# WalkSensor_V3_0.net
KiCad netlist of a schematic drawn in EAGLE
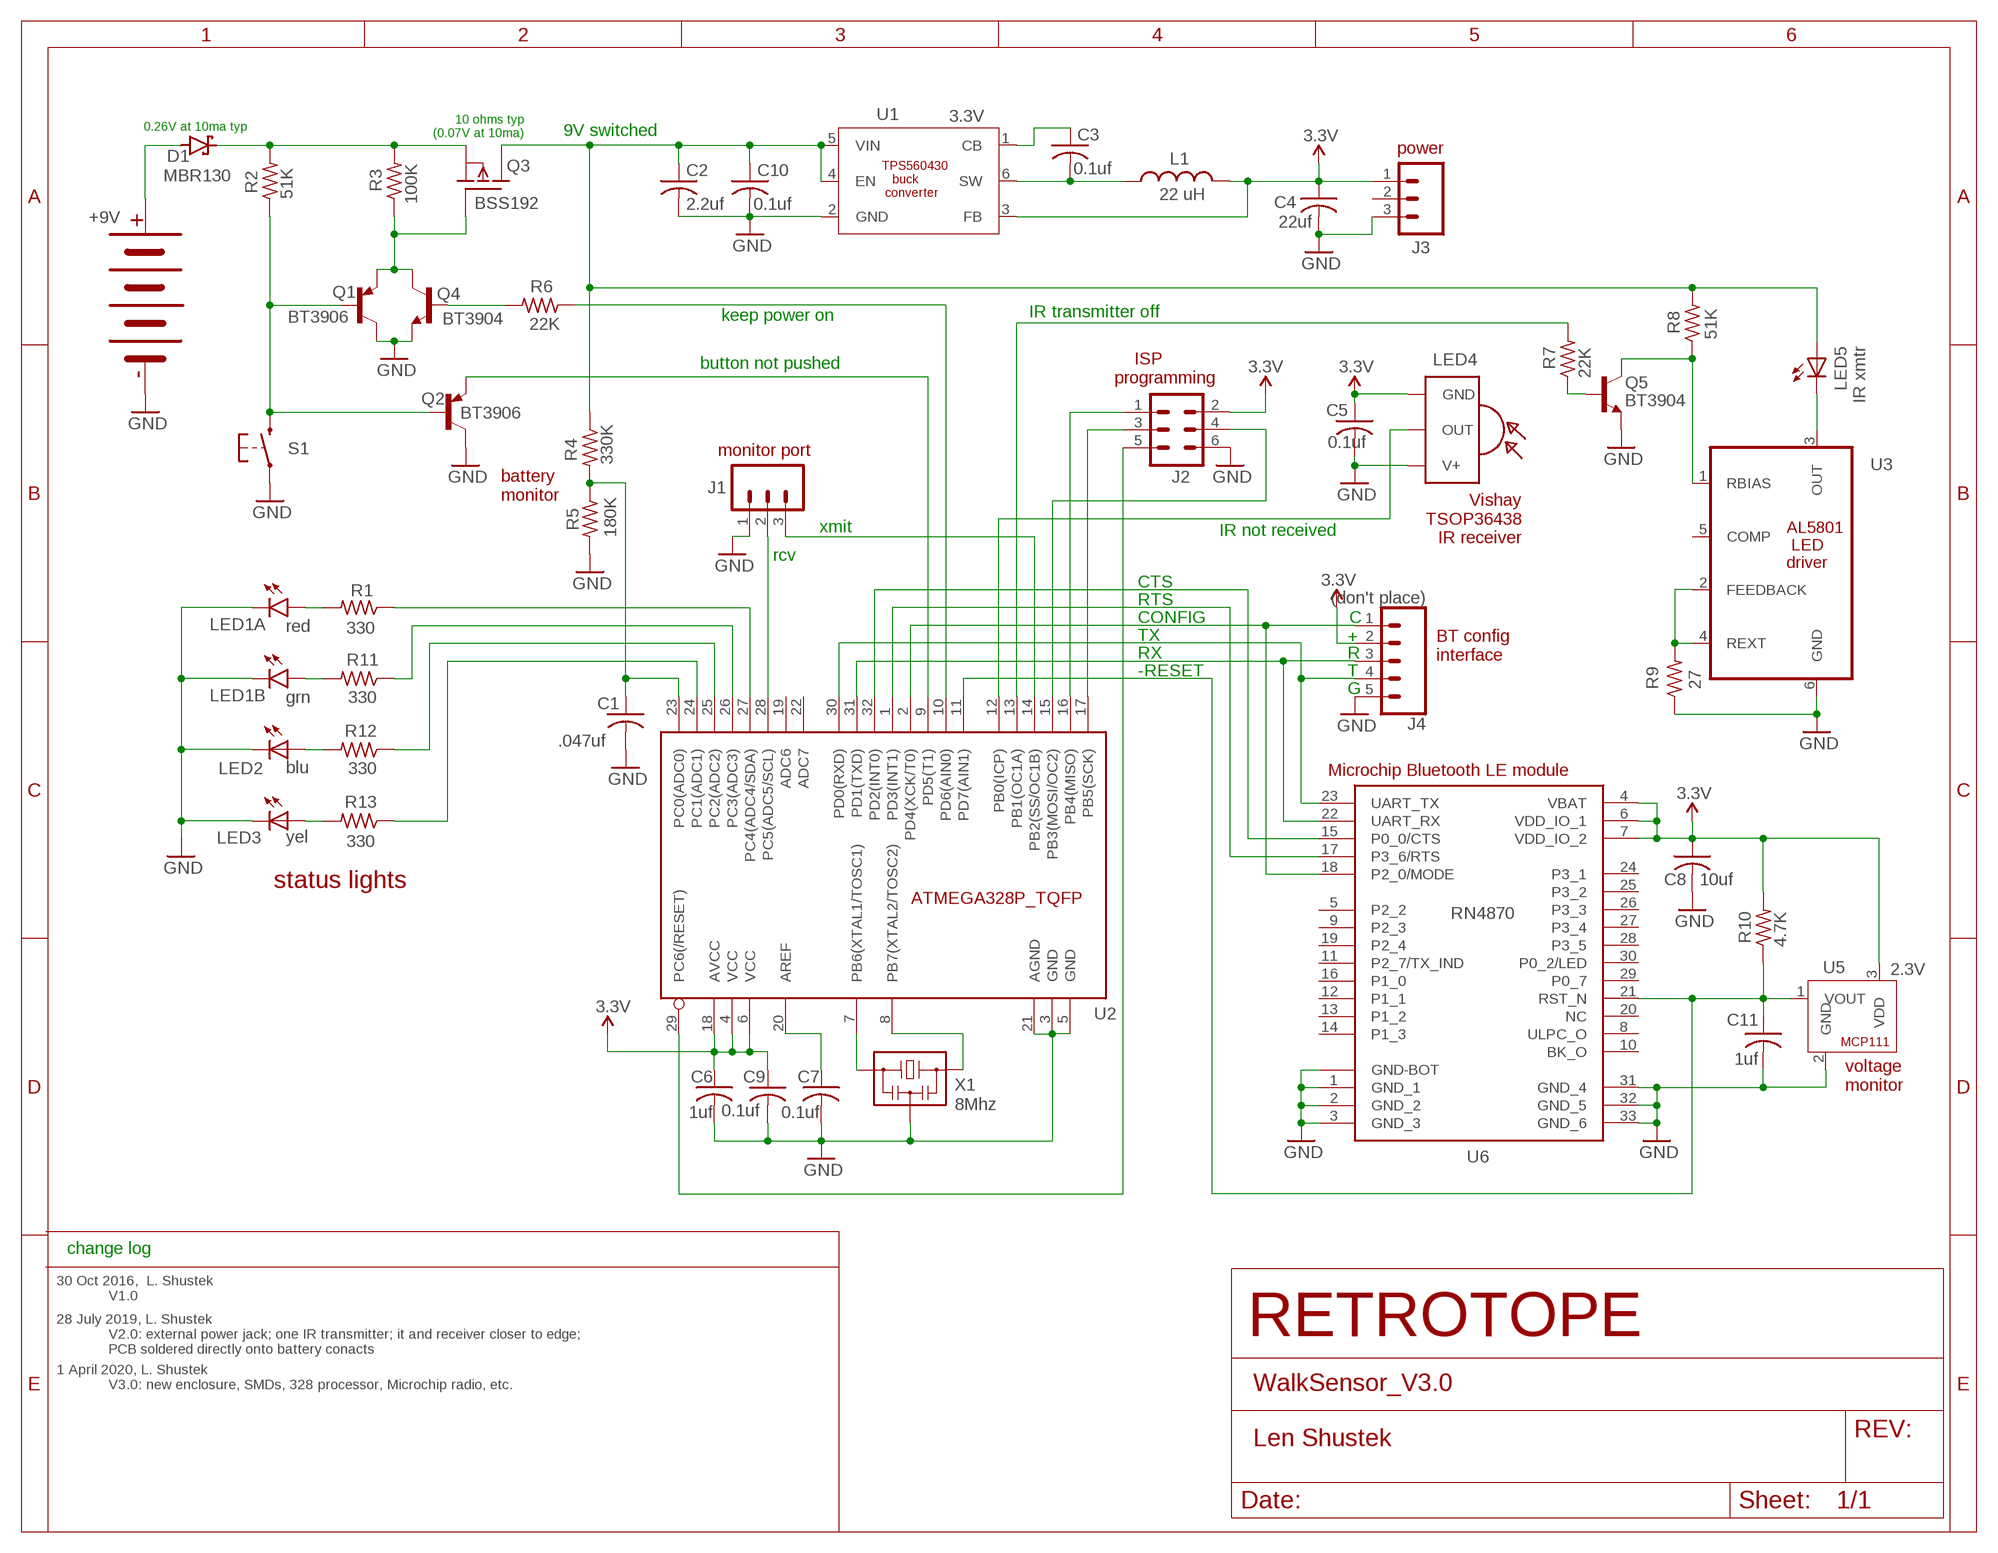
[diagram p0: schematic, sheet 1]

(export (version "E")
  (design (tool "Eeschema 10.0.6"))
  (components
    (comp (ref "B1")
      (value "9V battery wires")
      (footprint "eagle-import:4-CELL-BATTERY")
      (libsource (lib "eagle-import") (part "4-CELL-BATTERY"))
    )
    (comp (ref "C1")
      (value ".047uf")
      (footprint "eagle-import:C0805")
      (libsource (lib "eagle-import") (part "C-USC0805"))
    )
    (comp (ref "C2")
      (value "2.2uf")
      (footprint "eagle-import:C1210")
      (libsource (lib "eagle-import") (part "C-USC1210"))
    )
    (comp (ref "C3")
      (value "0.1uf")
      (footprint "eagle-import:C0805")
      (libsource (lib "eagle-import") (part "C-USC0805"))
    )
    (comp (ref "C4")
      (value "22uf")
      (footprint "eagle-import:C1210")
      (libsource (lib "eagle-import") (part "C-USC1210"))
    )
    (comp (ref "C5")
      (value "0.1uf")
      (footprint "eagle-import:C0805")
      (libsource (lib "eagle-import") (part "C-USC0805"))
    )
    (comp (ref "C6")
      (value "1uf")
      (footprint "eagle-import:C0805")
      (libsource (lib "eagle-import") (part "C-USC0805"))
    )
    (comp (ref "C7")
      (value "0.1uf")
      (footprint "eagle-import:C0805")
      (libsource (lib "eagle-import") (part "C-USC0805"))
    )
    (comp (ref "C8")
      (value "10uf")
      (footprint "eagle-import:C1210")
      (libsource (lib "eagle-import") (part "C-USC1210"))
    )
    (comp (ref "C9")
      (value "0.1uf")
      (footprint "eagle-import:C0805")
      (libsource (lib "eagle-import") (part "C-USC0805"))
    )
    (comp (ref "C10")
      (value "0.1uf")
      (footprint "eagle-import:C0805")
      (libsource (lib "eagle-import") (part "C-USC0805"))
    )
    (comp (ref "C11")
      (value "1uf")
      (footprint "eagle-import:C0805")
      (libsource (lib "eagle-import") (part "C-USC0805"))
    )
    (comp (ref "D1")
      (value "MBR130")
      (footprint "eagle-import:SOD123-2")
      (libsource (lib "eagle-import") (part "DIODE,SCHOTTKY"))
    )
    (comp (ref "J1")
      (value "(don't place)")
      (footprint "eagle-import:1X03")
      (libsource (lib "eagle-import") (part "CONN_03"))
    )
    (comp (ref "J2")
      (value "ISP pgm connector")
      (footprint "eagle-import:2X3_SMT")
      (libsource (lib "eagle-import") (part "CONN_03X22X3_SMT"))
    )
    (comp (ref "J3")
      (value "(don't place)")
      (footprint "eagle-import:1X03")
      (libsource (lib "eagle-import") (part "CONN_03"))
    )
    (comp (ref "J4")
      (value "(don't place)")
      (footprint "eagle-import:1X05")
      (libsource (lib "eagle-import") (part "CONN_05"))
    )
    (comp (ref "L1")
      (value "22 uH")
      (footprint "eagle-import:L1812")
      (libsource (lib "eagle-import") (part "L-USL1812"))
    )
    (comp (ref "LED1")
      (value "red/grn")
      (footprint "eagle-import:P-LCC4-1")
      (libsource (lib "eagle-import") (part "LED_DUALP-LCC4-1"))
    )
    (comp (ref "LED2")
      (value "blu")
      (footprint "eagle-import:LED_PLCC-2")
      (libsource (lib "eagle-import") (part "LEDPLCC-2"))
    )
    (comp (ref "LED3")
      (value "yel")
      (footprint "eagle-import:LED_PLCC-2")
      (libsource (lib "eagle-import") (part "LEDPLCC-2"))
    )
    (comp (ref "LED4")
      (value "IR rcvr")
      (footprint "eagle-import:VISHAY_TSOP_SMD_SIDE")
      (libsource (lib "eagle-import") (part "IR_RCVRVISHAY_TSOP_SMD_SIDE"))
    )
    (comp (ref "LED5")
      (value "IR xmtr")
      (footprint "eagle-import:LED_VISHAY_VSMB2948")
      (libsource (lib "eagle-import") (part "LEDLED_VISHAY_VSMB2948"))
    )
    (comp (ref "Q1")
      (value "BT3906")
      (footprint "eagle-import:SOT23-3")
      (libsource (lib "eagle-import") (part "PNP_TRANSISTORSOT23-3"))
    )
    (comp (ref "Q2")
      (value "BT3906")
      (footprint "eagle-import:SOT23-3")
      (libsource (lib "eagle-import") (part "PNP_TRANSISTORSOT23-3"))
    )
    (comp (ref "Q3")
      (value "BSS192")
      (footprint "eagle-import:SOT89")
      (libsource (lib "eagle-import") (part "VP3203SOP89"))
    )
    (comp (ref "Q4")
      (value "BT3904")
      (footprint "eagle-import:SOT23-3")
      (libsource (lib "eagle-import") (part "NPN-TRANSISTORSOT23-3"))
    )
    (comp (ref "Q5")
      (value "BT3904")
      (footprint "eagle-import:SOT23-3")
      (libsource (lib "eagle-import") (part "NPN-TRANSISTORSOT23-3"))
    )
    (comp (ref "R1")
      (value "330")
      (footprint "eagle-import:M0805")
      (libsource (lib "eagle-import") (part "R-US_M0805"))
    )
    (comp (ref "R2")
      (value "51K")
      (footprint "eagle-import:M0805")
      (libsource (lib "eagle-import") (part "R-US_M0805"))
    )
    (comp (ref "R3")
      (value "100K")
      (footprint "eagle-import:M0805")
      (libsource (lib "eagle-import") (part "R-US_M0805"))
    )
    (comp (ref "R4")
      (value "330K")
      (footprint "eagle-import:M0805")
      (libsource (lib "eagle-import") (part "R-US_M0805"))
    )
    (comp (ref "R5")
      (value "180K")
      (footprint "eagle-import:M0805")
      (libsource (lib "eagle-import") (part "R-US_M0805"))
    )
    (comp (ref "R6")
      (value "22K")
      (footprint "eagle-import:M0805")
      (libsource (lib "eagle-import") (part "R-US_M0805"))
    )
    (comp (ref "R7")
      (value "22K")
      (footprint "eagle-import:M0805")
      (libsource (lib "eagle-import") (part "R-US_M0805"))
    )
    (comp (ref "R8")
      (value "51K")
      (footprint "eagle-import:M0805")
      (libsource (lib "eagle-import") (part "R-US_M0805"))
    )
    (comp (ref "R9")
      (value "27")
      (footprint "eagle-import:M0805")
      (libsource (lib "eagle-import") (part "R-US_M0805"))
    )
    (comp (ref "R10")
      (value "4.7K")
      (footprint "eagle-import:M0805")
      (libsource (lib "eagle-import") (part "R-US_M0805"))
    )
    (comp (ref "R11")
      (value "330")
      (footprint "eagle-import:M0805")
      (libsource (lib "eagle-import") (part "R-US_M0805"))
    )
    (comp (ref "R12")
      (value "330")
      (footprint "eagle-import:M0805")
      (libsource (lib "eagle-import") (part "R-US_M0805"))
    )
    (comp (ref "R13")
      (value "330")
      (footprint "eagle-import:M0805")
      (libsource (lib "eagle-import") (part "R-US_M0805"))
    )
    (comp (ref "S1")
      (value "pushbutton")
      (footprint "eagle-import:SWITCH_C&K_GULLWING")
      (libsource (lib "eagle-import") (part "PUSHBUTTON-SPSTC&K_GULLWING"))
    )
    (comp (ref "U1")
      (value "3.3V")
      (footprint "eagle-import:SOT23-6")
      (libsource (lib "eagle-import") (part "TPS560430"))
    )
    (comp (ref "U2")
      (value "ATMEGA328P_TQFP")
      (footprint "eagle-import:TQFP32-08")
      (libsource (lib "eagle-import") (part "ATMEGA328P_TQFP"))
    )
    (comp (ref "U3")
      (value "AL5801")
      (footprint "eagle-import:SOT95P280X130-6N")
      (fields (field (name "MPN") "ZXGD3005E6TA"))
      (libsource (lib "eagle-import") (part "AL5801"))
    )
    (comp (ref "U5")
      (value "2.3V")
      (footprint "eagle-import:SC70-3-R")
      (libsource (lib "eagle-import") (part "MCP111SC-70"))
    )
    (comp (ref "U6")
      (value "RN4870")
      (footprint "eagle-import:RN4870")
      (libsource (lib "eagle-import") (part "RN4870-V_RM118LJS1"))
    )
    (comp (ref "X1")
      (value "8Mhz")
      (footprint "eagle-import:CSTNE")
      (libsource (lib "eagle-import") (part "CSTCRCSTNE"))
    )
  )
  (nets
    (net (code "1") (name "3.3V") (class "Default")
      (node (ref "C4") (pin "1") (pinfunction "1_1") (pintype "passive"))
      (node (ref "C5") (pin "1") (pinfunction "1_1") (pintype "passive"))
      (node (ref "C6") (pin "1") (pinfunction "1_1") (pintype "passive"))
      (node (ref "C8") (pin "1") (pinfunction "1_1") (pintype "passive"))
      (node (ref "C9") (pin "1") (pinfunction "1_1") (pintype "passive"))
      (node (ref "J2") (pin "2") (pinfunction "2_2") (pintype "bidirectional"))
      (node (ref "J3") (pin "1") (pinfunction "1_1") (pintype "passive"))
      (node (ref "J4") (pin "2") (pinfunction "2_2") (pintype "passive"))
      (node (ref "L1") (pin "2") (pinfunction "2_2") (pintype "passive"))
      (node (ref "LED4") (pin "P$1") (pinfunction "GND_P$1") (pintype "bidirectional"))
      (node (ref "R10") (pin "2") (pinfunction "2_2") (pintype "passive"))
      (node (ref "U1") (pin "3") (pinfunction "FB_3") (pintype "bidirectional"))
      (node (ref "U2") (pin "18") (pinfunction "AVCC_18") (pintype "bidirectional"))
      (node (ref "U2") (pin "4") (pinfunction "VCC_4") (pintype "bidirectional"))
      (node (ref "U2") (pin "6") (pinfunction "VCC_6") (pintype "bidirectional"))
      (node (ref "U5") (pin "3") (pinfunction "VDD_3") (pintype "bidirectional"))
      (node (ref "U6") (pin "4") (pinfunction "VBAT_4") (pintype "power_in"))
      (node (ref "U6") (pin "6") (pinfunction "VDD_IO_1_6") (pintype "power_in"))
      (node (ref "U6") (pin "7") (pinfunction "VDD_IO_2_7") (pintype "power_in"))
    )
    (net (code "2") (name "GND") (class "Default")
      (node (ref "B1") (pin "P$1") (pinfunction "P$1_P$1") (pintype "bidirectional"))
      (node (ref "C1") (pin "2") (pinfunction "2_2") (pintype "passive"))
      (node (ref "C10") (pin "2") (pinfunction "2_2") (pintype "passive"))
      (node (ref "C11") (pin "2") (pinfunction "2_2") (pintype "passive"))
      (node (ref "C2") (pin "2") (pinfunction "2_2") (pintype "passive"))
      (node (ref "C4") (pin "2") (pinfunction "2_2") (pintype "passive"))
      (node (ref "C5") (pin "2") (pinfunction "2_2") (pintype "passive"))
      (node (ref "C6") (pin "2") (pinfunction "2_2") (pintype "passive"))
      (node (ref "C7") (pin "2") (pinfunction "2_2") (pintype "passive"))
      (node (ref "C8") (pin "2") (pinfunction "2_2") (pintype "passive"))
      (node (ref "C9") (pin "2") (pinfunction "2_2") (pintype "passive"))
      (node (ref "J1") (pin "1") (pinfunction "1_1") (pintype "passive"))
      (node (ref "J2") (pin "6") (pinfunction "6_6") (pintype "bidirectional"))
      (node (ref "J3") (pin "3") (pinfunction "3_3") (pintype "passive"))
      (node (ref "J4") (pin "5") (pinfunction "5_5") (pintype "passive"))
      (node (ref "LED1") (pin "P$1") (pinfunction "C_P$1") (pintype "passive"))
      (node (ref "LED1") (pin "P$4") (pinfunction "C_P$4") (pintype "passive"))
      (node (ref "LED2") (pin "P$2") (pinfunction "C_P$2") (pintype "passive"))
      (node (ref "LED3") (pin "P$2") (pinfunction "C_P$2") (pintype "passive"))
      (node (ref "LED4") (pin "P$3") (pinfunction "V+_P$3") (pintype "bidirectional"))
      (node (ref "Q1") (pin "3") (pinfunction "C_3") (pintype "passive"))
      (node (ref "Q2") (pin "3") (pinfunction "C_3") (pintype "passive"))
      (node (ref "Q4") (pin "2") (pinfunction "E_2") (pintype "passive"))
      (node (ref "Q5") (pin "2") (pinfunction "E_2") (pintype "passive"))
      (node (ref "R5") (pin "2") (pinfunction "2_2") (pintype "passive"))
      (node (ref "R9") (pin "1") (pinfunction "1_1") (pintype "passive"))
      (node (ref "S1") (pin "P$1") (pinfunction "1_P$1") (pintype "passive"))
      (node (ref "S1") (pin "P$2") (pinfunction "1_P$2") (pintype "passive"))
      (node (ref "U1") (pin "2") (pinfunction "GND_2") (pintype "bidirectional"))
      (node (ref "U2") (pin "21") (pinfunction "AGND_21") (pintype "bidirectional"))
      (node (ref "U2") (pin "3") (pinfunction "GND_3") (pintype "bidirectional"))
      (node (ref "U2") (pin "5") (pinfunction "GND_5") (pintype "bidirectional"))
      (node (ref "U3") (pin "6") (pinfunction "GND_6") (pintype "power_in"))
      (node (ref "U5") (pin "2") (pinfunction "GND_2") (pintype "bidirectional"))
      (node (ref "U6") (pin "1") (pinfunction "GND_1_1") (pintype "power_in"))
      (node (ref "U6") (pin "2") (pinfunction "GND_2_2") (pintype "power_in"))
      (node (ref "U6") (pin "3") (pinfunction "GND_3_3") (pintype "power_in"))
      (node (ref "U6") (pin "31") (pinfunction "GND_4_31") (pintype "power_in"))
      (node (ref "U6") (pin "32") (pinfunction "GND_5_32") (pintype "power_in"))
      (node (ref "U6") (pin "33") (pinfunction "GND_6_33") (pintype "power_in"))
      (node (ref "U6") (pin "GND") (pinfunction "GND-BOT_GND") (pintype "power_in"))
      (node (ref "X1") (pin "P$2") (pinfunction "2_P$2") (pintype "passive"))
    )
    (net (code "3") (name "Net-(D1-A)") (class "Default")
      (node (ref "B1") (pin "P$2") (pinfunction "P$2_P$2") (pintype "bidirectional"))
      (node (ref "D1") (pin "P$1") (pinfunction "A_P$1") (pintype "passive"))
    )
    (net (code "4") (name "Net-(D1-C)") (class "Default")
      (node (ref "D1") (pin "P$2") (pinfunction "C_P$2") (pintype "passive"))
      (node (ref "Q3") (pin "3") (pinfunction "S_3") (pintype "passive"))
      (node (ref "R2") (pin "2") (pinfunction "2_2") (pintype "passive"))
      (node (ref "R3") (pin "2") (pinfunction "2_2") (pintype "passive"))
    )
    (net (code "5") (name "Net-(LED1A-A)") (class "Default")
      (node (ref "LED1") (pin "P$2") (pinfunction "A_P$2") (pintype "passive"))
      (node (ref "R1") (pin "2") (pinfunction "2_2") (pintype "passive"))
    )
    (net (code "6") (name "Net-(LED1B-A)") (class "Default")
      (node (ref "LED1") (pin "P$3") (pinfunction "A_P$3") (pintype "passive"))
      (node (ref "R11") (pin "2") (pinfunction "2_2") (pintype "passive"))
    )
    (net (code "7") (name "Net-(LED2-A)") (class "Default")
      (node (ref "LED2") (pin "P$1") (pinfunction "A_P$1") (pintype "passive"))
      (node (ref "R12") (pin "2") (pinfunction "2_2") (pintype "passive"))
    )
    (net (code "8") (name "Net-(LED3-A)") (class "Default")
      (node (ref "LED3") (pin "P$1") (pinfunction "A_P$1") (pintype "passive"))
      (node (ref "R13") (pin "2") (pinfunction "2_2") (pintype "passive"))
    )
    (net (code "9") (name "Net-(LED4-OUT)") (class "Default")
      (node (ref "LED4") (pin "P$4") (pinfunction "OUT_P$4") (pintype "bidirectional"))
      (node (ref "U2") (pin "12") (pinfunction "PB0(ICP)_12") (pintype "bidirectional"))
    )
    (net (code "10") (name "Net-(LED5-A)") (class "Default")
      (node (ref "C10") (pin "1") (pinfunction "1_1") (pintype "passive"))
      (node (ref "C2") (pin "1") (pinfunction "1_1") (pintype "passive"))
      (node (ref "LED5") (pin "P$2") (pinfunction "A_P$2") (pintype "passive"))
      (node (ref "Q3") (pin "2") (pinfunction "D_2") (pintype "passive"))
      (node (ref "Q3") (pin "2@1") (pinfunction "D_2@1") (pintype "passive"))
      (node (ref "R4") (pin "1") (pinfunction "1_1") (pintype "passive"))
      (node (ref "R8") (pin "2") (pinfunction "2_2") (pintype "passive"))
      (node (ref "U1") (pin "4") (pinfunction "EN_4") (pintype "bidirectional"))
      (node (ref "U1") (pin "5") (pinfunction "VIN_5") (pintype "bidirectional"))
    )
    (net (code "11") (name "Net-(LED5-C)") (class "Default")
      (node (ref "LED5") (pin "P$1") (pinfunction "C_P$1") (pintype "passive"))
      (node (ref "U3") (pin "3") (pinfunction "OUT_3") (pintype "passive"))
    )
    (net (code "12") (name "Net-(Q1-B)") (class "Default")
      (node (ref "Q1") (pin "1") (pinfunction "B_1") (pintype "passive"))
      (node (ref "Q2") (pin "1") (pinfunction "B_1") (pintype "passive"))
      (node (ref "R2") (pin "1") (pinfunction "1_1") (pintype "passive"))
      (node (ref "S1") (pin "P$3") (pinfunction "3_P$3") (pintype "passive"))
      (node (ref "S1") (pin "P$4") (pinfunction "3_P$4") (pintype "passive"))
    )
    (net (code "13") (name "Net-(Q1-E)") (class "Default")
      (node (ref "Q1") (pin "2") (pinfunction "E_2") (pintype "passive"))
      (node (ref "Q3") (pin "1") (pinfunction "G_1") (pintype "passive"))
      (node (ref "Q4") (pin "3") (pinfunction "C_3") (pintype "passive"))
      (node (ref "R3") (pin "1") (pinfunction "1_1") (pintype "passive"))
    )
    (net (code "14") (name "Net-(Q2-E)") (class "Default")
      (node (ref "Q2") (pin "2") (pinfunction "E_2") (pintype "passive"))
      (node (ref "U2") (pin "9") (pinfunction "PD5(T1)_9") (pintype "bidirectional"))
    )
    (net (code "15") (name "Net-(Q4-B)") (class "Default")
      (node (ref "Q4") (pin "1") (pinfunction "B_1") (pintype "passive"))
      (node (ref "R6") (pin "2") (pinfunction "2_2") (pintype "passive"))
    )
    (net (code "16") (name "Net-(Q5-B)") (class "Default")
      (node (ref "Q5") (pin "1") (pinfunction "B_1") (pintype "passive"))
      (node (ref "R7") (pin "1") (pinfunction "1_1") (pintype "passive"))
    )
    (net (code "17") (name "Net-(Q5-C)") (class "Default")
      (node (ref "Q5") (pin "3") (pinfunction "C_3") (pintype "passive"))
      (node (ref "R8") (pin "1") (pinfunction "1_1") (pintype "passive"))
      (node (ref "U3") (pin "1") (pinfunction "RBIAS_1") (pintype "passive"))
    )
    (net (code "18") (name "Net-(U1-CB)") (class "Default")
      (node (ref "C3") (pin "1") (pinfunction "1_1") (pintype "passive"))
      (node (ref "U1") (pin "1") (pinfunction "CB_1") (pintype "bidirectional"))
    )
    (net (code "19") (name "Net-(U1-SW)") (class "Default")
      (node (ref "C3") (pin "2") (pinfunction "2_2") (pintype "passive"))
      (node (ref "L1") (pin "1") (pinfunction "1_1") (pintype "passive"))
      (node (ref "U1") (pin "6") (pinfunction "SW_6") (pintype "bidirectional"))
    )
    (net (code "20") (name "Net-(U2-AREF)") (class "Default")
      (node (ref "C7") (pin "1") (pinfunction "1_1") (pintype "passive"))
      (node (ref "U2") (pin "20") (pinfunction "AREF_20") (pintype "bidirectional"))
    )
    (net (code "21") (name "Net-(U2-PB1(OC1A))") (class "Default")
      (node (ref "R7") (pin "2") (pinfunction "2_2") (pintype "passive"))
      (node (ref "U2") (pin "13") (pinfunction "PB1(OC1A)_13") (pintype "bidirectional"))
    )
    (net (code "22") (name "Net-(U2-PB2(SS{slash}OC1B))") (class "Default")
      (node (ref "J1") (pin "3") (pinfunction "3_3") (pintype "passive"))
      (node (ref "U2") (pin "14") (pinfunction "PB2(SS/OC1B)_14") (pintype "bidirectional"))
    )
    (net (code "23") (name "Net-(U2-PB3(MOSI{slash}OC2))") (class "Default")
      (node (ref "J2") (pin "4") (pinfunction "4_4") (pintype "bidirectional"))
      (node (ref "U2") (pin "15") (pinfunction "PB3(MOSI/OC2)_15") (pintype "bidirectional"))
    )
    (net (code "24") (name "Net-(U2-PB4(MISO))") (class "Default")
      (node (ref "J2") (pin "1") (pinfunction "1_1") (pintype "bidirectional"))
      (node (ref "U2") (pin "16") (pinfunction "PB4(MISO)_16") (pintype "bidirectional"))
    )
    (net (code "25") (name "Net-(U2-PB5(SCK))") (class "Default")
      (node (ref "J2") (pin "3") (pinfunction "3_3") (pintype "bidirectional"))
      (node (ref "U2") (pin "17") (pinfunction "PB5(SCK)_17") (pintype "bidirectional"))
    )
    (net (code "26") (name "Net-(U2-PB6(XTAL1{slash}TOSC1))") (class "Default")
      (node (ref "U2") (pin "7") (pinfunction "PB6(XTAL1/TOSC1)_7") (pintype "bidirectional"))
      (node (ref "X1") (pin "P$1") (pinfunction "1_P$1") (pintype "passive"))
    )
    (net (code "27") (name "Net-(U2-PB7(XTAL2{slash}TOSC2))") (class "Default")
      (node (ref "U2") (pin "8") (pinfunction "PB7(XTAL2/TOSC2)_8") (pintype "bidirectional"))
      (node (ref "X1") (pin "P$3") (pinfunction "3_P$3") (pintype "passive"))
    )
    (net (code "28") (name "Net-(U2-PC0(ADC0))") (class "Default")
      (node (ref "C1") (pin "1") (pinfunction "1_1") (pintype "passive"))
      (node (ref "R4") (pin "2") (pinfunction "2_2") (pintype "passive"))
      (node (ref "R5") (pin "1") (pinfunction "1_1") (pintype "passive"))
      (node (ref "U2") (pin "23") (pinfunction "PC0(ADC0)_23") (pintype "bidirectional"))
    )
    (net (code "29") (name "Net-(U2-PC1(ADC1))") (class "Default")
      (node (ref "R13") (pin "1") (pinfunction "1_1") (pintype "passive"))
      (node (ref "U2") (pin "24") (pinfunction "PC1(ADC1)_24") (pintype "bidirectional"))
    )
    (net (code "30") (name "Net-(U2-PC2(ADC2))") (class "Default")
      (node (ref "R12") (pin "1") (pinfunction "1_1") (pintype "passive"))
      (node (ref "U2") (pin "25") (pinfunction "PC2(ADC2)_25") (pintype "bidirectional"))
    )
    (net (code "31") (name "Net-(U2-PC3(ADC3))") (class "Default")
      (node (ref "R11") (pin "1") (pinfunction "1_1") (pintype "passive"))
      (node (ref "U2") (pin "26") (pinfunction "PC3(ADC3)_26") (pintype "bidirectional"))
    )
    (net (code "32") (name "Net-(U2-PC4(ADC4{slash}SDA))") (class "Default")
      (node (ref "R1") (pin "1") (pinfunction "1_1") (pintype "passive"))
      (node (ref "U2") (pin "27") (pinfunction "PC4(ADC4/SDA)_27") (pintype "bidirectional"))
    )
    (net (code "33") (name "Net-(U2-PC5(ADC5{slash}SCL))") (class "Default")
      (node (ref "J1") (pin "2") (pinfunction "2_2") (pintype "passive"))
      (node (ref "U2") (pin "28") (pinfunction "PC5(ADC5/SCL)_28") (pintype "bidirectional"))
    )
    (net (code "34") (name "Net-(U2-PC6({slash}RESET))") (class "Default")
      (node (ref "J2") (pin "5") (pinfunction "5_5") (pintype "bidirectional"))
      (node (ref "U2") (pin "29") (pinfunction "PC6(/RESET)_29") (pintype "bidirectional"))
    )
    (net (code "35") (name "Net-(U2-PD0(RXD))") (class "Default")
      (node (ref "J4") (pin "4") (pinfunction "4_4") (pintype "passive"))
      (node (ref "U2") (pin "30") (pinfunction "PD0(RXD)_30") (pintype "bidirectional"))
      (node (ref "U6") (pin "23") (pinfunction "UART_TX_23") (pintype "bidirectional"))
    )
    (net (code "36") (name "Net-(U2-PD1(TXD))") (class "Default")
      (node (ref "J4") (pin "3") (pinfunction "3_3") (pintype "passive"))
      (node (ref "U2") (pin "31") (pinfunction "PD1(TXD)_31") (pintype "bidirectional"))
      (node (ref "U6") (pin "22") (pinfunction "UART_RX_22") (pintype "bidirectional"))
    )
    (net (code "37") (name "Net-(U2-PD2(INT0))") (class "Default")
      (node (ref "U2") (pin "32") (pinfunction "PD2(INT0)_32") (pintype "bidirectional"))
      (node (ref "U6") (pin "15") (pinfunction "P0_0/CTS_15") (pintype "bidirectional"))
    )
    (net (code "38") (name "Net-(U2-PD3(INT1))") (class "Default")
      (node (ref "U2") (pin "1") (pinfunction "PD3(INT1)_1") (pintype "bidirectional"))
      (node (ref "U6") (pin "17") (pinfunction "P3_6/RTS_17") (pintype "bidirectional"))
    )
    (net (code "39") (name "Net-(U2-PD4(XCK{slash}T0))") (class "Default")
      (node (ref "J4") (pin "1") (pinfunction "1_1") (pintype "passive"))
      (node (ref "U2") (pin "2") (pinfunction "PD4(XCK/T0)_2") (pintype "bidirectional"))
      (node (ref "U6") (pin "18") (pinfunction "P2_0/MODE_18") (pintype "bidirectional"))
    )
    (net (code "40") (name "Net-(U2-PD6(AIN0))") (class "Default")
      (node (ref "R6") (pin "1") (pinfunction "1_1") (pintype "passive"))
      (node (ref "U2") (pin "10") (pinfunction "PD6(AIN0)_10") (pintype "bidirectional"))
    )
    (net (code "41") (name "Net-(U2-PD7(AIN1))") (class "Default")
      (node (ref "C11") (pin "1") (pinfunction "1_1") (pintype "passive"))
      (node (ref "R10") (pin "1") (pinfunction "1_1") (pintype "passive"))
      (node (ref "U2") (pin "11") (pinfunction "PD7(AIN1)_11") (pintype "bidirectional"))
      (node (ref "U5") (pin "1") (pinfunction "VOUT_1") (pintype "bidirectional"))
      (node (ref "U6") (pin "21") (pinfunction "RST_N_21") (pintype "bidirectional"))
    )
    (net (code "42") (name "Net-(U3-FEEDBACK)") (class "Default")
      (node (ref "R9") (pin "2") (pinfunction "2_2") (pintype "passive"))
      (node (ref "U3") (pin "2") (pinfunction "FEEDBACK_2") (pintype "passive"))
      (node (ref "U3") (pin "4") (pinfunction "REXT_4") (pintype "passive"))
    )
    (net (code "43") (name "unconnected-(J3-Pad2)") (class "Default")
      (node (ref "J3") (pin "2") (pinfunction "2_2") (pintype "passive"))
    )
    (net (code "44") (name "unconnected-(U2-ADC6-Pad19)") (class "Default")
      (node (ref "U2") (pin "19") (pinfunction "ADC6_19") (pintype "bidirectional"))
    )
    (net (code "45") (name "unconnected-(U2-ADC7-Pad22)") (class "Default")
      (node (ref "U2") (pin "22") (pinfunction "ADC7_22") (pintype "bidirectional"))
    )
    (net (code "46") (name "unconnected-(U3-COMP-Pad5)") (class "Default")
      (node (ref "U3") (pin "5") (pinfunction "COMP_5") (pintype "no_connect"))
    )
    (net (code "47") (name "unconnected-(U6-BK_O-Pad10)") (class "Default")
      (node (ref "U6") (pin "10") (pinfunction "BK_O_10") (pintype "bidirectional"))
    )
    (net (code "48") (name "unconnected-(U6-NC-Pad20)") (class "Default")
      (node (ref "U6") (pin "20") (pinfunction "NC_20") (pintype "no_connect"))
    )
    (net (code "49") (name "unconnected-(U6-P0_2{slash}LED-Pad30)") (class "Default")
      (node (ref "U6") (pin "30") (pinfunction "P0_2/LED_30") (pintype "bidirectional"))
    )
    (net (code "50") (name "unconnected-(U6-P0_7-Pad29)") (class "Default")
      (node (ref "U6") (pin "29") (pinfunction "P0_7_29") (pintype "bidirectional"))
    )
    (net (code "51") (name "unconnected-(U6-P1_0-Pad16)") (class "Default")
      (node (ref "U6") (pin "16") (pinfunction "P1_0_16") (pintype "bidirectional"))
    )
    (net (code "52") (name "unconnected-(U6-P1_1-Pad12)") (class "Default")
      (node (ref "U6") (pin "12") (pinfunction "P1_1_12") (pintype "bidirectional"))
    )
    (net (code "53") (name "unconnected-(U6-P1_2-Pad13)") (class "Default")
      (node (ref "U6") (pin "13") (pinfunction "P1_2_13") (pintype "bidirectional"))
    )
    (net (code "54") (name "unconnected-(U6-P1_3-Pad14)") (class "Default")
      (node (ref "U6") (pin "14") (pinfunction "P1_3_14") (pintype "bidirectional"))
    )
    (net (code "55") (name "unconnected-(U6-P2_2-Pad5)") (class "Default")
      (node (ref "U6") (pin "5") (pinfunction "P2_2_5") (pintype "bidirectional"))
    )
    (net (code "56") (name "unconnected-(U6-P2_3-Pad9)") (class "Default")
      (node (ref "U6") (pin "9") (pinfunction "P2_3_9") (pintype "bidirectional"))
    )
    (net (code "57") (name "unconnected-(U6-P2_4-Pad19)") (class "Default")
      (node (ref "U6") (pin "19") (pinfunction "P2_4_19") (pintype "bidirectional"))
    )
    (net (code "58") (name "unconnected-(U6-P2_7{slash}TX_IND-Pad11)") (class "Default")
      (node (ref "U6") (pin "11") (pinfunction "P2_7/TX_IND_11") (pintype "bidirectional"))
    )
    (net (code "59") (name "unconnected-(U6-P3_1-Pad24)") (class "Default")
      (node (ref "U6") (pin "24") (pinfunction "P3_1_24") (pintype "bidirectional"))
    )
    (net (code "60") (name "unconnected-(U6-P3_2-Pad25)") (class "Default")
      (node (ref "U6") (pin "25") (pinfunction "P3_2_25") (pintype "bidirectional"))
    )
    (net (code "61") (name "unconnected-(U6-P3_3-Pad26)") (class "Default")
      (node (ref "U6") (pin "26") (pinfunction "P3_3_26") (pintype "bidirectional"))
    )
    (net (code "62") (name "unconnected-(U6-P3_4-Pad27)") (class "Default")
      (node (ref "U6") (pin "27") (pinfunction "P3_4_27") (pintype "bidirectional"))
    )
    (net (code "63") (name "unconnected-(U6-P3_5-Pad28)") (class "Default")
      (node (ref "U6") (pin "28") (pinfunction "P3_5_28") (pintype "bidirectional"))
    )
    (net (code "64") (name "unconnected-(U6-ULPC_O-Pad8)") (class "Default")
      (node (ref "U6") (pin "8") (pinfunction "ULPC_O_8") (pintype "bidirectional"))
    )
  )
)
